# 24VSensing.net
KiCad netlist of a schematic drawn in Altium Designer
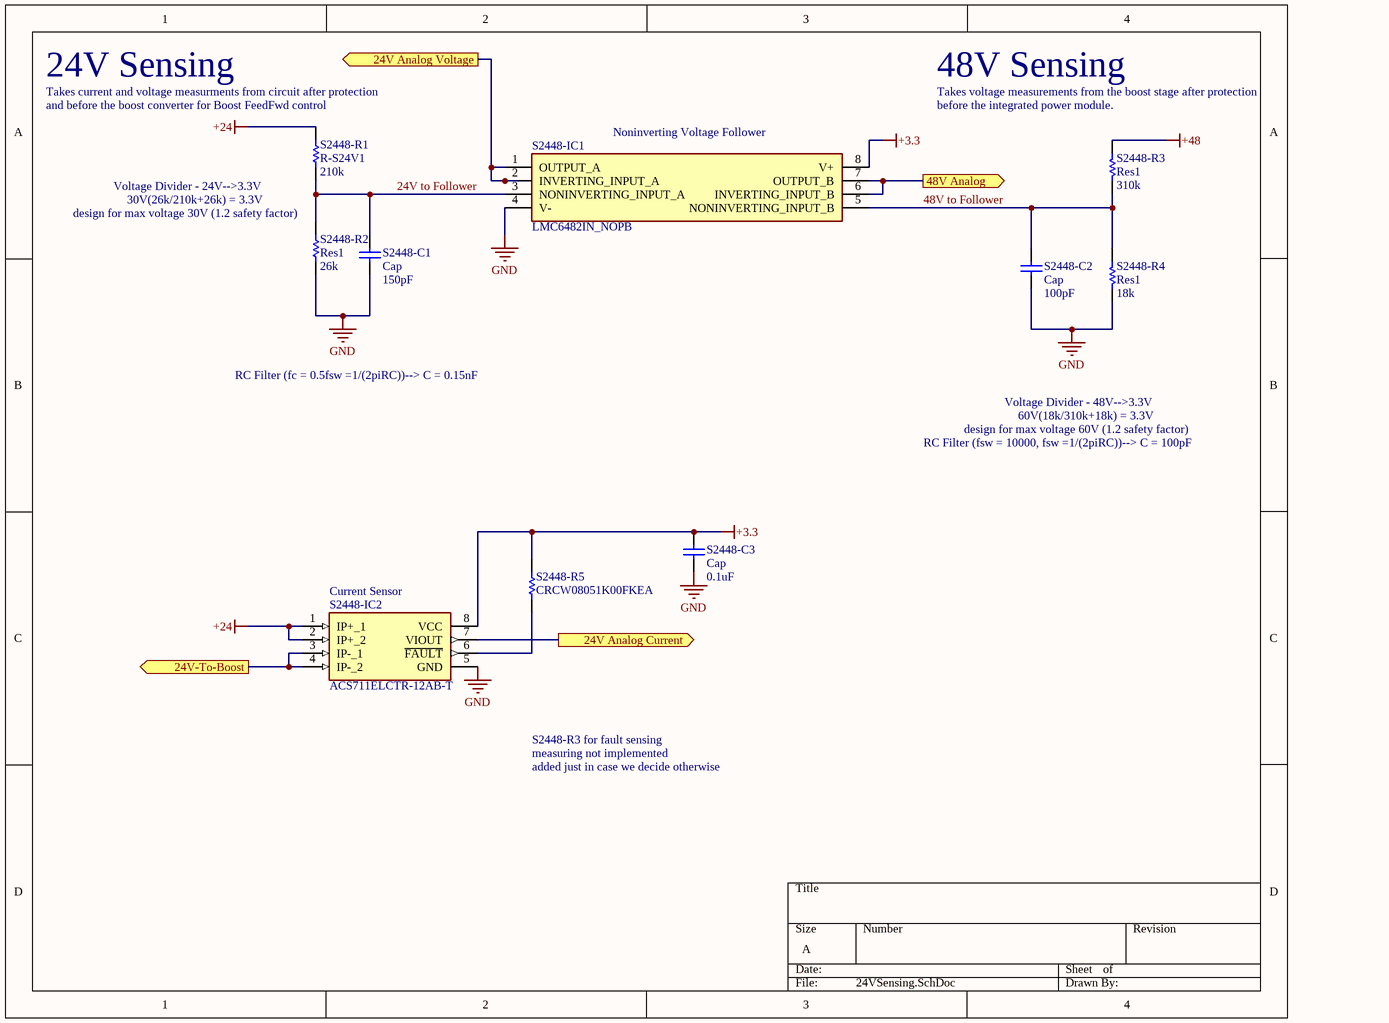
[diagram p0: 24VSensing.SchDoc]

(export (version "E")
  (design (tool "Eeschema 10.0.6"))
  (components
    (comp (ref "S2448-C1")
      (value "Cap")
      (footprint "RAD-0.3")
      (description "Capacitor")
      (fields (field (name "ALTIUM_VALUE") "150pF") (field (name "PUBLISHER") "Altium Limited"))
      (libsource (lib "Miscellaneous Devices") (part "Cap"))
    )
    (comp (ref "S2448-C2")
      (value "Cap")
      (footprint "RAD-0.3")
      (description "Capacitor")
      (fields (field (name "ALTIUM_VALUE") "100pF") (field (name "PUBLISHER") "Altium Limited"))
      (libsource (lib "Miscellaneous Devices") (part "Cap"))
    )
    (comp (ref "S2448-C3")
      (value "Cap")
      (footprint "RAD-0.3")
      (description "Capacitor")
      (fields (field (name "ALTIUM_VALUE") "0.1uF") (field (name "PUBLISHER") "Altium Limited"))
      (libsource (lib "Miscellaneous Devices") (part "Cap"))
    )
    (comp (ref "S2448-IC1")
      (value "LMC6482IN_NOPB")
      (footprint "SamacSys:DIP794W53P254L959H508Q8N")
      (description "Integrated Circuit")
      (fields
        (field (name "MANUFACTURER_PART_NUMBER") "LMC6482IN/NOPB")
        (field (name "MOUSER PART NUMBER") "926-LMC6482IN/NOPB")
      )
      (libsource (lib "*") (part "LMC6482IN_NOPB"))
    )
    (comp (ref "S2448-IC2")
      (value "ACS711ELCTR-12AB-T")
      (footprint "SamacSys:SOIC127P600X175-8N")
      (description "Integrated Circuit")
      (libsource (lib "*") (part "ACS711ELCTR-12AB-T"))
    )
    (comp (ref "S2448-R1")
      (value "R-S24V1")
      (footprint "AXIAL-0.3")
      (description "Resistor")
      (fields (field (name "ALTIUM_VALUE") "210k") (field (name "PUBLISHER") "Altium Limited"))
      (libsource (lib "Miscellaneous Devices") (part "Res1"))
    )
    (comp (ref "S2448-R2")
      (value "Res1")
      (footprint "AXIAL-0.3")
      (description "Resistor")
      (fields (field (name "ALTIUM_VALUE") "26k") (field (name "PUBLISHER") "Altium Limited"))
      (libsource (lib "Miscellaneous Devices") (part "Res1"))
    )
    (comp (ref "S2448-R3")
      (value "Res1")
      (footprint "AXIAL-0.3")
      (description "Resistor")
      (fields (field (name "ALTIUM_VALUE") "310k") (field (name "PUBLISHER") "Altium Limited"))
      (libsource (lib "Miscellaneous Devices") (part "Res1"))
    )
    (comp (ref "S2448-R4")
      (value "Res1")
      (footprint "AXIAL-0.3")
      (description "Resistor")
      (fields (field (name "ALTIUM_VALUE") "18k") (field (name "PUBLISHER") "Altium Limited"))
      (libsource (lib "Miscellaneous Devices") (part "Res1"))
    )
    (comp (ref "S2448-R5")
      (value "CRCW08051K00FKEA")
      (footprint "RESC2013X50X30NL20T20")
      (fields (field (name "MANUFACTURER") "Vishay Dale"))
      (libsource (lib "Altium Content Vault") (part "RES"))
    )
  )
  (nets
    (net (code "1") (name "+3.3") (class "Default")
      (node (ref "S2448-C3") (pin "2") (pinfunction "2_2") (pintype "passive"))
      (node (ref "S2448-IC1") (pin "8") (pinfunction "V+_8") (pintype "passive"))
      (node (ref "S2448-IC2") (pin "8") (pinfunction "VCC_8") (pintype "power_in"))
      (node (ref "S2448-R5") (pin "2") (pinfunction "2_2") (pintype "passive"))
    )
    (net (code "2") (name "+24") (class "Default")
      (node (ref "S2448-IC2") (pin "1") (pinfunction "IP+_1_1") (pintype "input"))
      (node (ref "S2448-IC2") (pin "2") (pinfunction "IP+_2_2") (pintype "input"))
      (node (ref "S2448-R1") (pin "2") (pinfunction "2_2") (pintype "passive"))
    )
    (net (code "3") (name "+48") (class "Default")
      (node (ref "S2448-R3") (pin "2") (pinfunction "2_2") (pintype "passive"))
    )
    (net (code "4") (name "/24V Analog Current") (class "Default")
      (node (ref "S2448-IC2") (pin "7") (pinfunction "VIOUT_7") (pintype "output"))
    )
    (net (code "5") (name "/24V Analog Voltage") (class "Default")
      (node (ref "S2448-IC1") (pin "1") (pinfunction "OUTPUT_A_1") (pintype "passive"))
      (node (ref "S2448-IC1") (pin "2") (pinfunction "INVERTING_INPUT_A_2") (pintype "passive"))
    )
    (net (code "6") (name "/24V to Follower") (class "Default")
      (node (ref "S2448-C1") (pin "2") (pinfunction "2_2") (pintype "passive"))
      (node (ref "S2448-IC1") (pin "3") (pinfunction "NONINVERTING_INPUT_A_3") (pintype "passive"))
      (node (ref "S2448-R1") (pin "1") (pinfunction "1_1") (pintype "passive"))
      (node (ref "S2448-R2") (pin "2") (pinfunction "2_2") (pintype "passive"))
    )
    (net (code "7") (name "/24V-To-Boost") (class "Default")
      (node (ref "S2448-IC2") (pin "3") (pinfunction "IP-_1_3") (pintype "input"))
      (node (ref "S2448-IC2") (pin "4") (pinfunction "IP-_2_4") (pintype "input"))
    )
    (net (code "8") (name "/48V Analog") (class "Default")
      (node (ref "S2448-IC1") (pin "6") (pinfunction "INVERTING_INPUT_B_6") (pintype "passive"))
      (node (ref "S2448-IC1") (pin "7") (pinfunction "OUTPUT_B_7") (pintype "passive"))
    )
    (net (code "9") (name "/48V to Follower") (class "Default")
      (node (ref "S2448-C2") (pin "2") (pinfunction "2_2") (pintype "passive"))
      (node (ref "S2448-IC1") (pin "5") (pinfunction "NONINVERTING_INPUT_B_5") (pintype "passive"))
      (node (ref "S2448-R3") (pin "1") (pinfunction "1_1") (pintype "passive"))
      (node (ref "S2448-R4") (pin "2") (pinfunction "2_2") (pintype "passive"))
    )
    (net (code "10") (name "GND") (class "Default")
      (node (ref "S2448-C1") (pin "1") (pinfunction "1_1") (pintype "passive"))
      (node (ref "S2448-C2") (pin "1") (pinfunction "1_1") (pintype "passive"))
      (node (ref "S2448-C3") (pin "1") (pinfunction "1_1") (pintype "passive"))
      (node (ref "S2448-IC1") (pin "4") (pinfunction "V-_4") (pintype "passive"))
      (node (ref "S2448-IC2") (pin "5") (pinfunction "GND_5") (pintype "power_in"))
      (node (ref "S2448-R2") (pin "1") (pinfunction "1_1") (pintype "passive"))
      (node (ref "S2448-R4") (pin "1") (pinfunction "1_1") (pintype "passive"))
    )
    (net (code "11") (name "Net-(S2448-IC2-~{FAULT})") (class "Default")
      (node (ref "S2448-IC2") (pin "6") (pinfunction "~{FAULT}_6") (pintype "output"))
      (node (ref "S2448-R5") (pin "1") (pinfunction "1_1") (pintype "passive"))
    )
  )
)
